# PB1_PSU.net
KiCad netlist of a schematic drawn in EAGLE
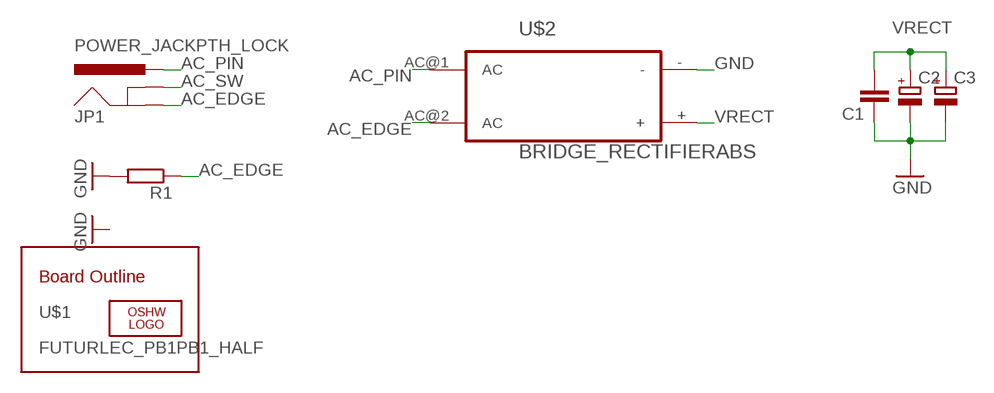
[diagram p0: schematic, sheet 1]

(export (version "E")
  (design (tool "Eeschema 10.0.6"))
  (components
    (comp (ref "C1")
      (value "C-EUC0805")
      (footprint "eagle-import:C0805")
      (libsource (lib "eagle-import") (part "C-EUC0805"))
    )
    (comp (ref "C2")
      (value "CPOL-EUE2.5-7")
      (footprint "eagle-import:E2,5-7")
      (libsource (lib "eagle-import") (part "CPOL-EUE2.5-7"))
    )
    (comp (ref "C3")
      (value "CPOL-EUE5-10.5")
      (footprint "eagle-import:E5-10,5")
      (libsource (lib "eagle-import") (part "CPOL-EUE5-10.5"))
    )
    (comp (ref "JP1")
      (value "POWER_JACKPTH_LOCK")
      (footprint "eagle-import:POWER_JACK_PTH_LOCK")
      (libsource (lib "eagle-import") (part "POWER_JACKPTH_LOCK"))
    )
    (comp (ref "LOGO1")
      (value "OSHW_LOGO_8MILX0200-NT")
      (footprint "eagle-import:OSHW_8X200_NOTEXT")
      (libsource (lib "eagle-import") (part "OSHW_LOGO_8MILX0200-NT"))
    )
    (comp (ref "R1")
      (value "R-EU_R0805")
      (footprint "eagle-import:R0805")
      (libsource (lib "eagle-import") (part "R-EU_R0805"))
    )
    (comp (ref "U$1")
      (value "FUTURLEC_PB1PB1_HALF")
      (footprint "eagle-import:FUTURLEC_PB1_HALF")
      (libsource (lib "eagle-import") (part "FUTURLEC_PB1PB1_HALF"))
    )
    (comp (ref "U$2")
      (value "BRIDGE_RECTIFIERABS")
      (footprint "eagle-import:ABS")
      (libsource (lib "eagle-import") (part "BRIDGE_RECTIFIERABS"))
    )
  )
  (nets
    (net (code "1") (name "/AC_EDGE") (class "Default")
      (node (ref "JP1") (pin "GND") (pinfunction "GND_GND") (pintype "bidirectional"))
      (node (ref "R1") (pin "1") (pinfunction "1_1") (pintype "passive"))
      (node (ref "U$2") (pin "AC@2") (pinfunction "AC_AC@2") (pintype "bidirectional"))
    )
    (net (code "2") (name "/AC_PIN") (class "Default")
      (node (ref "JP1") (pin "PWR") (pinfunction "PWR_PWR") (pintype "bidirectional"))
      (node (ref "U$2") (pin "AC@1") (pinfunction "AC_AC@1") (pintype "bidirectional"))
    )
    (net (code "3") (name "/AC_SW") (class "Default")
      (node (ref "JP1") (pin "GNDBREAK") (pinfunction "GNDBREAK_GNDBREAK") (pintype "bidirectional"))
    )
    (net (code "4") (name "/VRECT") (class "Default")
      (node (ref "C1") (pin "2") (pinfunction "2_2") (pintype "passive"))
      (node (ref "C2") (pin "+") (pinfunction "+_+") (pintype "passive"))
      (node (ref "C3") (pin "+") (pinfunction "+_+") (pintype "passive"))
      (node (ref "U$2") (pin "+") (pinfunction "+_+") (pintype "bidirectional"))
    )
    (net (code "5") (name "GND") (class "Default")
      (node (ref "C1") (pin "1") (pinfunction "1_1") (pintype "passive"))
      (node (ref "C2") (pin "-") (pinfunction "-_-") (pintype "passive"))
      (node (ref "C3") (pin "-") (pinfunction "-_-") (pintype "passive"))
      (node (ref "R1") (pin "2") (pinfunction "2_2") (pintype "passive"))
      (node (ref "U$2") (pin "-") (pinfunction "-_-") (pintype "bidirectional"))
    )
  )
)
